# Comportamiento_central.net
KiCad netlist of a schematic drawn in EAGLE
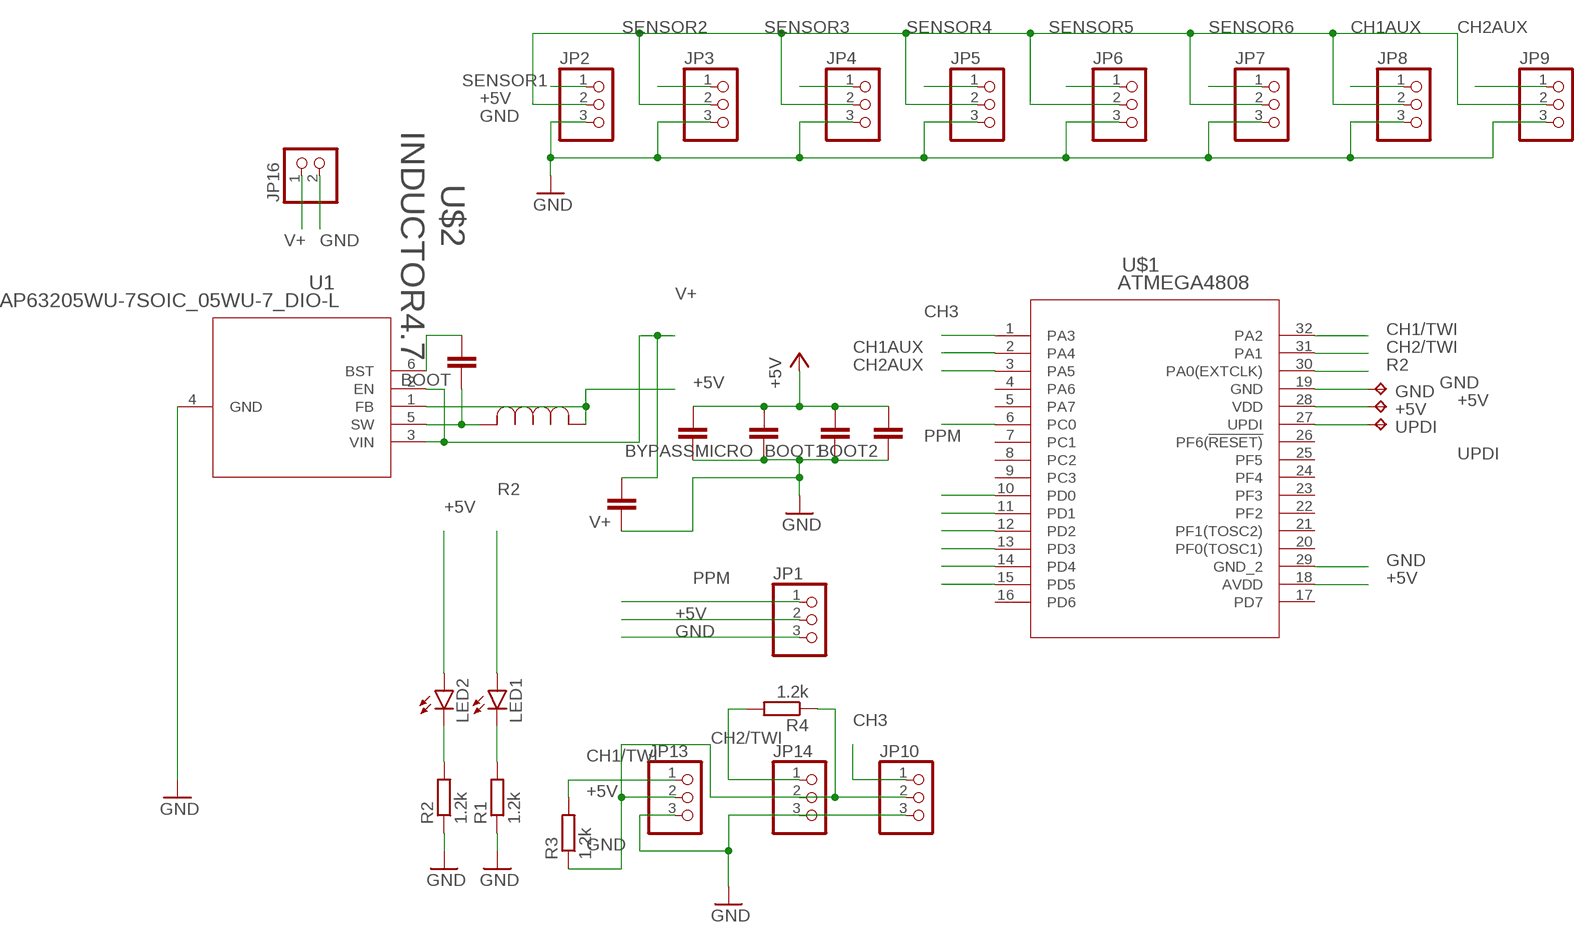
[diagram p0: schematic, sheet 1]

(export (version "E")
  (design (tool "Eeschema 10.0.6"))
  (components
    (comp (ref "+5V")
      (value "TPB1,27")
      (footprint "eagle-import:B1,27")
      (libsource (lib "eagle-import") (part "TPB1,27"))
    )
    (comp (ref "BOOT")
      (value "C-EUC0402")
      (footprint "eagle-import:C0402")
      (libsource (lib "eagle-import") (part "C-EUC0402"))
    )
    (comp (ref "BOOT1")
      (value "C-EUC0402")
      (footprint "eagle-import:C0402")
      (libsource (lib "eagle-import") (part "C-EUC0402"))
    )
    (comp (ref "BOOT2")
      (value "C-EUC0402")
      (footprint "eagle-import:C0402")
      (libsource (lib "eagle-import") (part "C-EUC0402"))
    )
    (comp (ref "BYPASSMICRO")
      (value "C-EUC0603")
      (footprint "eagle-import:C0603")
      (libsource (lib "eagle-import") (part "C-EUC0603"))
    )
    (comp (ref "BYPASSMICRO2")
      (value "C-EUC0603")
      (footprint "eagle-import:C0603")
      (libsource (lib "eagle-import") (part "C-EUC0603"))
    )
    (comp (ref "GND")
      (value "TPB1,27")
      (footprint "eagle-import:B1,27")
      (libsource (lib "eagle-import") (part "TPB1,27"))
    )
    (comp (ref "JP1")
      (value "PINHD-1X03_2.54-S")
      (footprint "eagle-import:1X03-S")
      (libsource (lib "eagle-import") (part "PINHD-1X03_2.54-S"))
    )
    (comp (ref "JP2")
      (value "PINHD-1X03_2.54-S")
      (footprint "eagle-import:1X03-S")
      (libsource (lib "eagle-import") (part "PINHD-1X03_2.54-S"))
    )
    (comp (ref "JP3")
      (value "PINHD-1X03_2.54-S")
      (footprint "eagle-import:1X03-S")
      (libsource (lib "eagle-import") (part "PINHD-1X03_2.54-S"))
    )
    (comp (ref "JP4")
      (value "PINHD-1X03_2.54-S")
      (footprint "eagle-import:1X03-S")
      (libsource (lib "eagle-import") (part "PINHD-1X03_2.54-S"))
    )
    (comp (ref "JP5")
      (value "PINHD-1X03_2.54-S")
      (footprint "eagle-import:1X03-S")
      (libsource (lib "eagle-import") (part "PINHD-1X03_2.54-S"))
    )
    (comp (ref "JP6")
      (value "PINHD-1X03_2.54-S")
      (footprint "eagle-import:1X03-S")
      (libsource (lib "eagle-import") (part "PINHD-1X03_2.54-S"))
    )
    (comp (ref "JP7")
      (value "PINHD-1X03_2.54-S")
      (footprint "eagle-import:1X03-S")
      (libsource (lib "eagle-import") (part "PINHD-1X03_2.54-S"))
    )
    (comp (ref "JP8")
      (value "PINHD-1X03_2.54-S")
      (footprint "eagle-import:1X03-S")
      (libsource (lib "eagle-import") (part "PINHD-1X03_2.54-S"))
    )
    (comp (ref "JP9")
      (value "PINHD-1X03_2.54-S")
      (footprint "eagle-import:1X03-S")
      (libsource (lib "eagle-import") (part "PINHD-1X03_2.54-S"))
    )
    (comp (ref "JP10")
      (value "PINHD-1X03_2.54-S")
      (footprint "eagle-import:1X03-S")
      (libsource (lib "eagle-import") (part "PINHD-1X03_2.54-S"))
    )
    (comp (ref "JP13")
      (value "PINHD-1X03_2.54-S")
      (footprint "eagle-import:1X03-S")
      (libsource (lib "eagle-import") (part "PINHD-1X03_2.54-S"))
    )
    (comp (ref "JP14")
      (value "PINHD-1X03_2.54-S")
      (footprint "eagle-import:1X03-S")
      (libsource (lib "eagle-import") (part "PINHD-1X03_2.54-S"))
    )
    (comp (ref "JP16")
      (value "PINHD-1X02_2.54-S")
      (footprint "eagle-import:1X02-S")
      (libsource (lib "eagle-import") (part "PINHD-1X02_2.54-S"))
    )
    (comp (ref "LED1")
      (value "LEDCHIPLED_0603")
      (footprint "eagle-import:CHIPLED_0603")
      (libsource (lib "eagle-import") (part "LEDCHIPLED_0603"))
    )
    (comp (ref "LED2")
      (value "LEDCHIPLED_0603")
      (footprint "eagle-import:CHIPLED_0603")
      (libsource (lib "eagle-import") (part "LEDCHIPLED_0603"))
    )
    (comp (ref "R1")
      (value "1.2k")
      (footprint "eagle-import:R0603")
      (libsource (lib "eagle-import") (part "R-EU_R0603"))
    )
    (comp (ref "R2")
      (value "1.2k")
      (footprint "eagle-import:R0603")
      (libsource (lib "eagle-import") (part "R-EU_R0603"))
    )
    (comp (ref "R3")
      (value "1.2k")
      (footprint "eagle-import:R0603")
      (libsource (lib "eagle-import") (part "R-EU_R0603"))
    )
    (comp (ref "R4")
      (value "1.2k")
      (footprint "eagle-import:R0603")
      (libsource (lib "eagle-import") (part "R-EU_R0603"))
    )
    (comp (ref "U$1")
      (value "ATMEGA4808")
      (footprint "eagle-import:QFP80P900X900X120-32N")
      (libsource (lib "eagle-import") (part "ATMEGA4808"))
    )
    (comp (ref "U$2")
      (value "INDUCTOR4.7")
      (footprint "eagle-import:IND_NRS5030T100MMGJ_TAY")
      (libsource (lib "eagle-import") (part "INDUCTOR4.7"))
    )
    (comp (ref "U1")
      (value "AP63205WU-7SOIC_05WU-7_DIO-L")
      (footprint "eagle-import:SOIC_05WU-7_DIO-L")
      (fields
        (field (name "MANUFACTURER_PART_NUMBER") "AP63205WU-7")
        (field (name "COPYRIGHT") "Copyright (C) 2018 Accelerated Designs. All rights reserved")
      )
      (libsource (lib "eagle-import") (part "AP63205WU-7SOIC_05WU-7_DIO-L"))
    )
    (comp (ref "UPDI")
      (value "TPB1,27")
      (footprint "eagle-import:B1,27")
      (libsource (lib "eagle-import") (part "TPB1,27"))
    )
    (comp (ref "V+")
      (value "C-EUC1206")
      (footprint "eagle-import:C1206")
      (libsource (lib "eagle-import") (part "C-EUC1206"))
    )
  )
  (nets
    (net (code "1") (name "+5V") (class "Default")
      (node (ref "+5V") (pin "TP") (pinfunction "TP_TP") (pintype "input"))
      (node (ref "BOOT1") (pin "2") (pinfunction "2_2") (pintype "passive"))
      (node (ref "BOOT2") (pin "2") (pinfunction "2_2") (pintype "passive"))
      (node (ref "BYPASSMICRO") (pin "2") (pinfunction "2_2") (pintype "passive"))
      (node (ref "BYPASSMICRO2") (pin "2") (pinfunction "2_2") (pintype "passive"))
      (node (ref "JP1") (pin "2") (pinfunction "2_2") (pintype "passive"))
      (node (ref "JP10") (pin "2") (pinfunction "2_2") (pintype "passive"))
      (node (ref "JP13") (pin "2") (pinfunction "2_2") (pintype "passive"))
      (node (ref "JP14") (pin "2") (pinfunction "2_2") (pintype "passive"))
      (node (ref "JP2") (pin "2") (pinfunction "2_2") (pintype "passive"))
      (node (ref "JP3") (pin "2") (pinfunction "2_2") (pintype "passive"))
      (node (ref "JP4") (pin "2") (pinfunction "2_2") (pintype "passive"))
      (node (ref "JP5") (pin "2") (pinfunction "2_2") (pintype "passive"))
      (node (ref "JP6") (pin "2") (pinfunction "2_2") (pintype "passive"))
      (node (ref "JP7") (pin "2") (pinfunction "2_2") (pintype "passive"))
      (node (ref "JP8") (pin "2") (pinfunction "2_2") (pintype "passive"))
      (node (ref "JP9") (pin "2") (pinfunction "2_2") (pintype "passive"))
      (node (ref "LED2") (pin "A") (pinfunction "A_A") (pintype "passive"))
      (node (ref "R3") (pin "1") (pinfunction "1_1") (pintype "passive"))
      (node (ref "R4") (pin "1") (pinfunction "1_1") (pintype "passive"))
      (node (ref "U$1") (pin "18") (pinfunction "AVDD_18") (pintype "power_in"))
      (node (ref "U$1") (pin "28") (pinfunction "VDD_28") (pintype "power_in"))
      (node (ref "U$2") (pin "1") (pinfunction "1_1") (pintype "passive"))
      (node (ref "U1") (pin "1") (pinfunction "FB_1") (pintype "passive"))
    )
    (net (code "2") (name "/CH1AUX") (class "Default")
      (node (ref "JP8") (pin "1") (pinfunction "1_1") (pintype "passive"))
      (node (ref "U$1") (pin "2") (pinfunction "PA4_2") (pintype "bidirectional"))
    )
    (net (code "3") (name "/CH1{slash}TWI") (class "Default")
      (node (ref "JP13") (pin "1") (pinfunction "1_1") (pintype "passive"))
      (node (ref "R3") (pin "2") (pinfunction "2_2") (pintype "passive"))
      (node (ref "U$1") (pin "32") (pinfunction "PA2_32") (pintype "bidirectional"))
    )
    (net (code "4") (name "/CH2AUX") (class "Default")
      (node (ref "JP9") (pin "1") (pinfunction "1_1") (pintype "passive"))
      (node (ref "U$1") (pin "3") (pinfunction "PA5_3") (pintype "bidirectional"))
    )
    (net (code "5") (name "/CH2{slash}TWI") (class "Default")
      (node (ref "JP14") (pin "1") (pinfunction "1_1") (pintype "passive"))
      (node (ref "R4") (pin "2") (pinfunction "2_2") (pintype "passive"))
      (node (ref "U$1") (pin "31") (pinfunction "PA1_31") (pintype "bidirectional"))
    )
    (net (code "6") (name "/CH3") (class "Default")
      (node (ref "JP10") (pin "1") (pinfunction "1_1") (pintype "passive"))
      (node (ref "U$1") (pin "1") (pinfunction "PA3_1") (pintype "bidirectional"))
    )
    (net (code "7") (name "/PPM") (class "Default")
      (node (ref "JP1") (pin "1") (pinfunction "1_1") (pintype "passive"))
      (node (ref "U$1") (pin "6") (pinfunction "PC0_6") (pintype "bidirectional"))
    )
    (net (code "8") (name "/R2") (class "Default")
      (node (ref "LED1") (pin "A") (pinfunction "A_A") (pintype "passive"))
      (node (ref "U$1") (pin "30") (pinfunction "PA0(EXTCLK)_30") (pintype "bidirectional"))
    )
    (net (code "9") (name "/SENSOR1") (class "Default")
      (node (ref "JP2") (pin "1") (pinfunction "1_1") (pintype "passive"))
      (node (ref "U$1") (pin "10") (pinfunction "PD0_10") (pintype "bidirectional"))
    )
    (net (code "10") (name "/SENSOR2") (class "Default")
      (node (ref "JP3") (pin "1") (pinfunction "1_1") (pintype "passive"))
      (node (ref "U$1") (pin "11") (pinfunction "PD1_11") (pintype "bidirectional"))
    )
    (net (code "11") (name "/SENSOR3") (class "Default")
      (node (ref "JP4") (pin "1") (pinfunction "1_1") (pintype "passive"))
      (node (ref "U$1") (pin "12") (pinfunction "PD2_12") (pintype "bidirectional"))
    )
    (net (code "12") (name "/SENSOR4") (class "Default")
      (node (ref "JP5") (pin "1") (pinfunction "1_1") (pintype "passive"))
      (node (ref "U$1") (pin "13") (pinfunction "PD3_13") (pintype "bidirectional"))
    )
    (net (code "13") (name "/SENSOR5") (class "Default")
      (node (ref "JP6") (pin "1") (pinfunction "1_1") (pintype "passive"))
      (node (ref "U$1") (pin "14") (pinfunction "PD4_14") (pintype "bidirectional"))
    )
    (net (code "14") (name "/SENSOR6") (class "Default")
      (node (ref "JP7") (pin "1") (pinfunction "1_1") (pintype "passive"))
      (node (ref "U$1") (pin "15") (pinfunction "PD5_15") (pintype "bidirectional"))
    )
    (net (code "15") (name "/UPDI") (class "Default")
      (node (ref "U$1") (pin "27") (pinfunction "UPDI_27") (pintype "bidirectional"))
      (node (ref "UPDI") (pin "TP") (pinfunction "TP_TP") (pintype "input"))
    )
    (net (code "16") (name "/V+") (class "Default")
      (node (ref "JP16") (pin "1") (pinfunction "1_1") (pintype "passive"))
      (node (ref "U1") (pin "2") (pinfunction "EN_2") (pintype "passive"))
      (node (ref "U1") (pin "3") (pinfunction "VIN_3") (pintype "passive"))
      (node (ref "V+") (pin "2") (pinfunction "2_2") (pintype "passive"))
    )
    (net (code "17") (name "GND") (class "Default")
      (node (ref "BOOT1") (pin "1") (pinfunction "1_1") (pintype "passive"))
      (node (ref "BOOT2") (pin "1") (pinfunction "1_1") (pintype "passive"))
      (node (ref "BYPASSMICRO") (pin "1") (pinfunction "1_1") (pintype "passive"))
      (node (ref "BYPASSMICRO2") (pin "1") (pinfunction "1_1") (pintype "passive"))
      (node (ref "GND") (pin "TP") (pinfunction "TP_TP") (pintype "input"))
      (node (ref "JP1") (pin "3") (pinfunction "3_3") (pintype "passive"))
      (node (ref "JP10") (pin "3") (pinfunction "3_3") (pintype "passive"))
      (node (ref "JP13") (pin "3") (pinfunction "3_3") (pintype "passive"))
      (node (ref "JP14") (pin "3") (pinfunction "3_3") (pintype "passive"))
      (node (ref "JP16") (pin "2") (pinfunction "2_2") (pintype "passive"))
      (node (ref "JP2") (pin "3") (pinfunction "3_3") (pintype "passive"))
      (node (ref "JP3") (pin "3") (pinfunction "3_3") (pintype "passive"))
      (node (ref "JP4") (pin "3") (pinfunction "3_3") (pintype "passive"))
      (node (ref "JP5") (pin "3") (pinfunction "3_3") (pintype "passive"))
      (node (ref "JP6") (pin "3") (pinfunction "3_3") (pintype "passive"))
      (node (ref "JP7") (pin "3") (pinfunction "3_3") (pintype "passive"))
      (node (ref "JP8") (pin "3") (pinfunction "3_3") (pintype "passive"))
      (node (ref "JP9") (pin "3") (pinfunction "3_3") (pintype "passive"))
      (node (ref "R1") (pin "1") (pinfunction "1_1") (pintype "passive"))
      (node (ref "R2") (pin "1") (pinfunction "1_1") (pintype "passive"))
      (node (ref "U$1") (pin "19") (pinfunction "GND_19") (pintype "passive"))
      (node (ref "U$1") (pin "29") (pinfunction "GND_2_29") (pintype "passive"))
      (node (ref "U1") (pin "4") (pinfunction "GND_4") (pintype "passive"))
      (node (ref "V+") (pin "1") (pinfunction "1_1") (pintype "passive"))
    )
    (net (code "18") (name "Net-(LED1-PadC)") (class "Default")
      (node (ref "LED1") (pin "C") (pinfunction "C_C") (pintype "passive"))
      (node (ref "R1") (pin "2") (pinfunction "2_2") (pintype "passive"))
    )
    (net (code "19") (name "Net-(LED2-PadC)") (class "Default")
      (node (ref "LED2") (pin "C") (pinfunction "C_C") (pintype "passive"))
      (node (ref "R2") (pin "2") (pinfunction "2_2") (pintype "passive"))
    )
    (net (code "20") (name "Net-(U1-BST)") (class "Default")
      (node (ref "BOOT") (pin "2") (pinfunction "2_2") (pintype "passive"))
      (node (ref "U1") (pin "6") (pinfunction "BST_6") (pintype "passive"))
    )
    (net (code "21") (name "Net-(U1-SW)") (class "Default")
      (node (ref "BOOT") (pin "1") (pinfunction "1_1") (pintype "passive"))
      (node (ref "U$2") (pin "2") (pinfunction "2_2") (pintype "passive"))
      (node (ref "U1") (pin "5") (pinfunction "SW_5") (pintype "passive"))
    )
    (net (code "22") (name "unconnected-(U$1-PA6-Pad4)") (class "Default")
      (node (ref "U$1") (pin "4") (pinfunction "PA6_4") (pintype "bidirectional"))
    )
    (net (code "23") (name "unconnected-(U$1-PA7-Pad5)") (class "Default")
      (node (ref "U$1") (pin "5") (pinfunction "PA7_5") (pintype "bidirectional"))
    )
    (net (code "24") (name "unconnected-(U$1-PC1-Pad7)") (class "Default")
      (node (ref "U$1") (pin "7") (pinfunction "PC1_7") (pintype "bidirectional"))
    )
    (net (code "25") (name "unconnected-(U$1-PC2-Pad8)") (class "Default")
      (node (ref "U$1") (pin "8") (pinfunction "PC2_8") (pintype "bidirectional"))
    )
    (net (code "26") (name "unconnected-(U$1-PC3-Pad9)") (class "Default")
      (node (ref "U$1") (pin "9") (pinfunction "PC3_9") (pintype "bidirectional"))
    )
    (net (code "27") (name "unconnected-(U$1-PD6-Pad16)") (class "Default")
      (node (ref "U$1") (pin "16") (pinfunction "PD6_16") (pintype "bidirectional"))
    )
    (net (code "28") (name "unconnected-(U$1-PD7-Pad17)") (class "Default")
      (node (ref "U$1") (pin "17") (pinfunction "PD7_17") (pintype "bidirectional"))
    )
    (net (code "29") (name "unconnected-(U$1-PF0(TOSC1)-Pad20)") (class "Default")
      (node (ref "U$1") (pin "20") (pinfunction "PF0(TOSC1)_20") (pintype "bidirectional"))
    )
    (net (code "30") (name "unconnected-(U$1-PF1(TOSC2)-Pad21)") (class "Default")
      (node (ref "U$1") (pin "21") (pinfunction "PF1(TOSC2)_21") (pintype "bidirectional"))
    )
    (net (code "31") (name "unconnected-(U$1-PF2-Pad22)") (class "Default")
      (node (ref "U$1") (pin "22") (pinfunction "PF2_22") (pintype "bidirectional"))
    )
    (net (code "32") (name "unconnected-(U$1-PF3-Pad23)") (class "Default")
      (node (ref "U$1") (pin "23") (pinfunction "PF3_23") (pintype "bidirectional"))
    )
    (net (code "33") (name "unconnected-(U$1-PF4-Pad24)") (class "Default")
      (node (ref "U$1") (pin "24") (pinfunction "PF4_24") (pintype "bidirectional"))
    )
    (net (code "34") (name "unconnected-(U$1-PF5-Pad25)") (class "Default")
      (node (ref "U$1") (pin "25") (pinfunction "PF5_25") (pintype "bidirectional"))
    )
    (net (code "35") (name "unconnected-(U$1-PF6(~{RESET})-Pad26)") (class "Default")
      (node (ref "U$1") (pin "26") (pinfunction "PF6(~{RESET})_26") (pintype "bidirectional"))
    )
  )
)
